# A131B.net
KiCad netlist of a schematic drawn in EAGLE
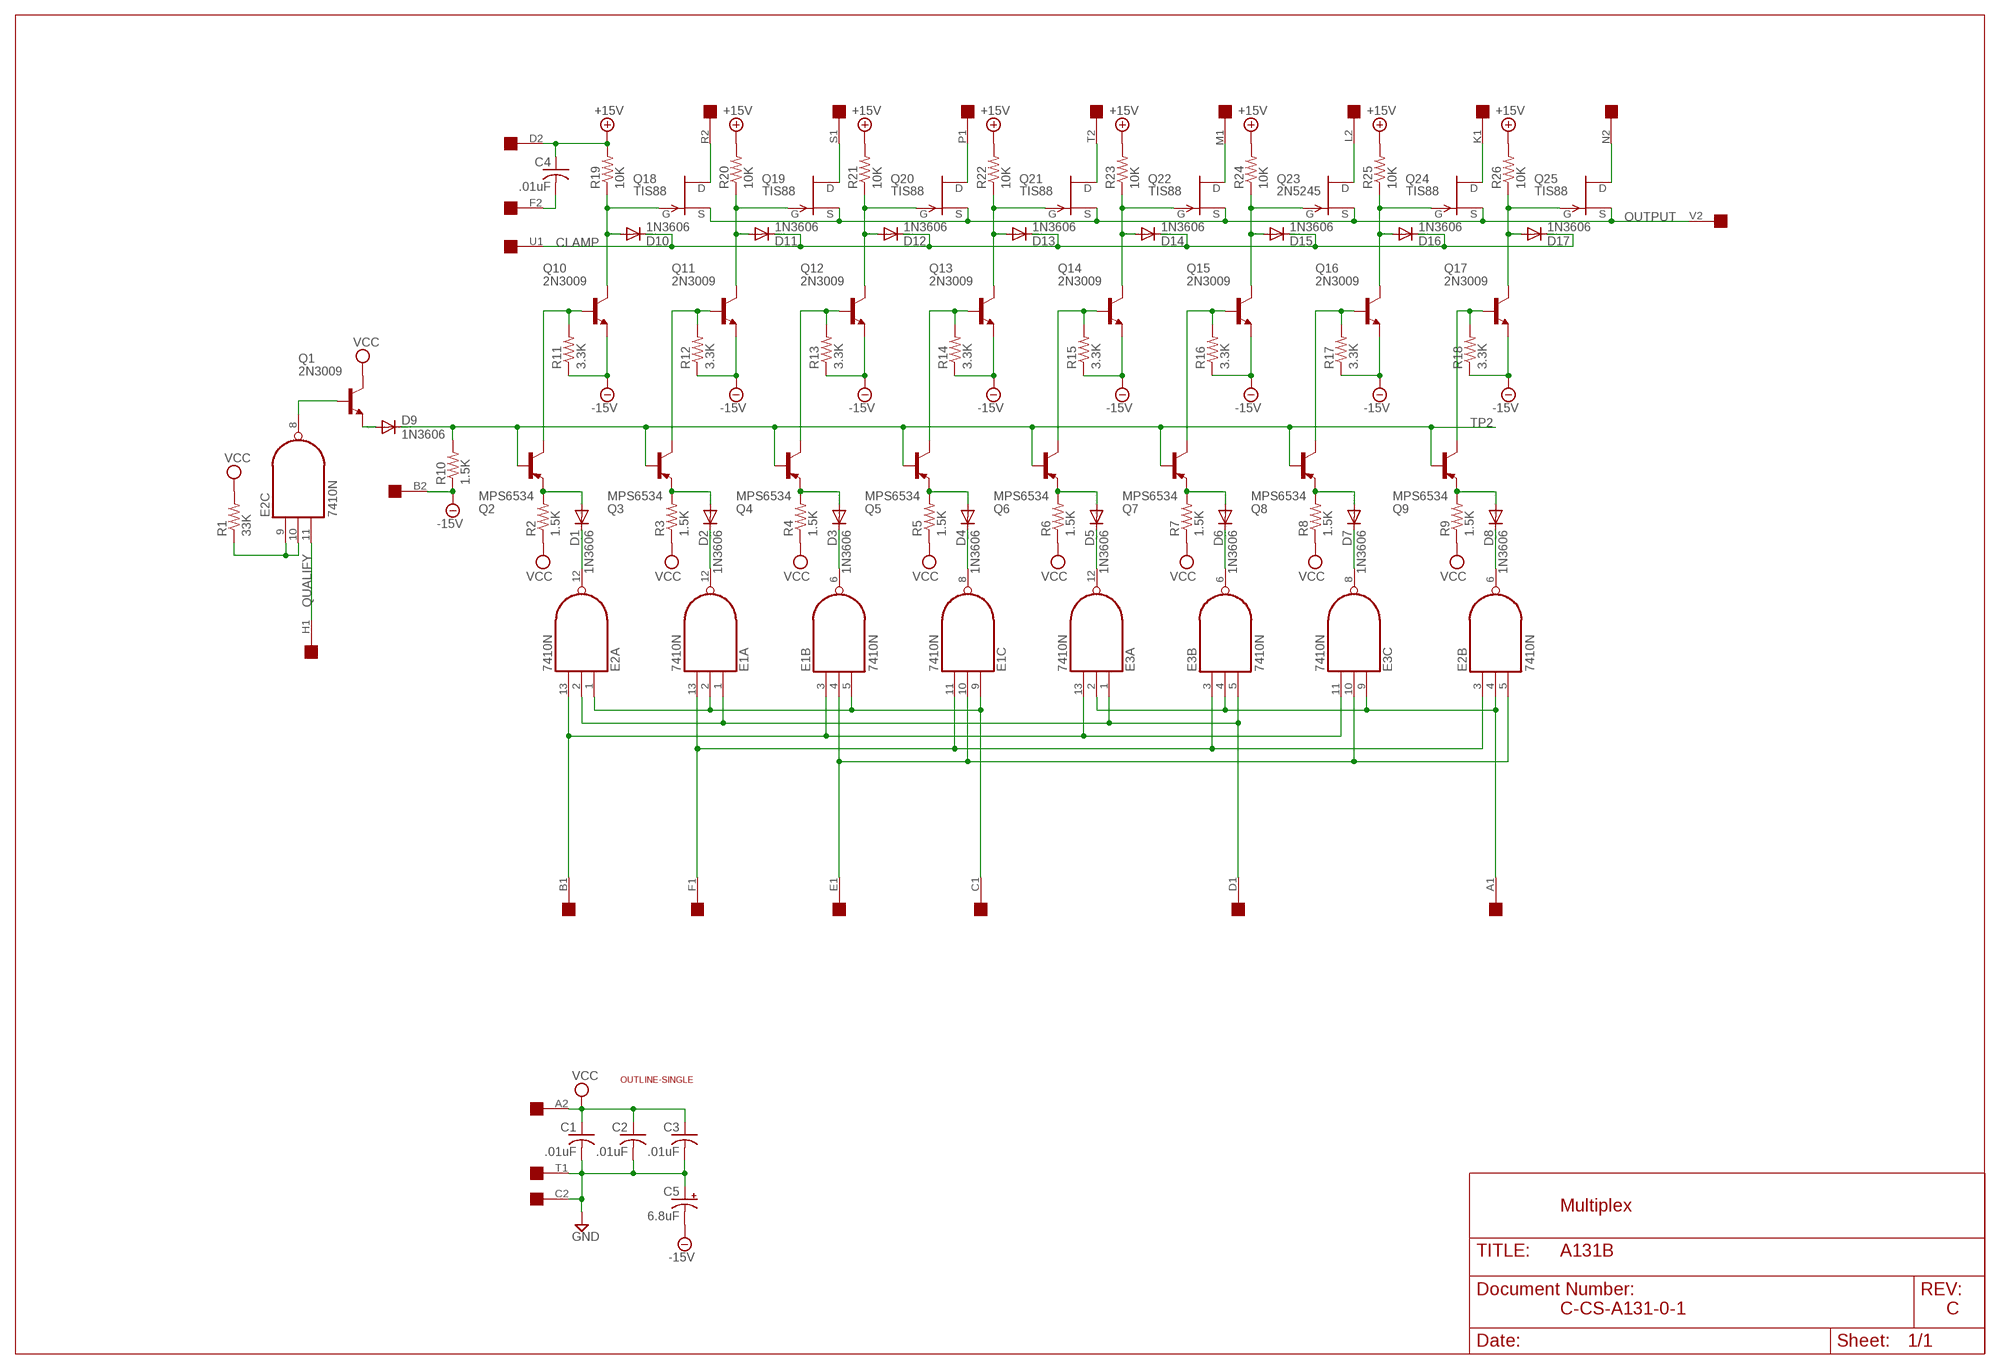
[diagram p0: schematic, sheet 1]

(export (version "E")
  (design (tool "Eeschema 10.0.6"))
  (components
    (comp (ref "C1")
      (value ".01uF")
      (footprint "eagle-import:C050-025X075")
      (libsource (lib "eagle-import") (part "C-US050-025X075"))
    )
    (comp (ref "C2")
      (value ".01uF")
      (footprint "eagle-import:C050-025X075")
      (libsource (lib "eagle-import") (part "C-US050-025X075"))
    )
    (comp (ref "C3")
      (value ".01uF")
      (footprint "eagle-import:C050-025X075")
      (libsource (lib "eagle-import") (part "C-US050-025X075"))
    )
    (comp (ref "C4")
      (value ".01uF")
      (footprint "eagle-import:C050-025X075")
      (libsource (lib "eagle-import") (part "C-US050-025X075"))
    )
    (comp (ref "C5")
      (value "6.8uF")
      (footprint "eagle-import:E12-8")
      (libsource (lib "eagle-import") (part "CPOL-USE20-8AXIAL"))
    )
    (comp (ref "D1")
      (value "1N3606")
      (footprint "eagle-import:DO35-10")
      (libsource (lib "eagle-import") (part "DIODE-DO35-10"))
    )
    (comp (ref "D2")
      (value "1N3606")
      (footprint "eagle-import:DO35-10")
      (libsource (lib "eagle-import") (part "DIODE-DO35-10"))
    )
    (comp (ref "D3")
      (value "1N3606")
      (footprint "eagle-import:DO35-10")
      (libsource (lib "eagle-import") (part "DIODE-DO35-10"))
    )
    (comp (ref "D4")
      (value "1N3606")
      (footprint "eagle-import:DO35-10")
      (libsource (lib "eagle-import") (part "DIODE-DO35-10"))
    )
    (comp (ref "D5")
      (value "1N3606")
      (footprint "eagle-import:DO35-10")
      (libsource (lib "eagle-import") (part "DIODE-DO35-10"))
    )
    (comp (ref "D6")
      (value "1N3606")
      (footprint "eagle-import:DO35-10")
      (libsource (lib "eagle-import") (part "DIODE-DO35-10"))
    )
    (comp (ref "D7")
      (value "1N3606")
      (footprint "eagle-import:DO35-10")
      (libsource (lib "eagle-import") (part "DIODE-DO35-10"))
    )
    (comp (ref "D8")
      (value "1N3606")
      (footprint "eagle-import:DO35-10")
      (libsource (lib "eagle-import") (part "DIODE-DO35-10"))
    )
    (comp (ref "D9")
      (value "1N3606")
      (footprint "eagle-import:DO35-10")
      (libsource (lib "eagle-import") (part "DIODE-DO35-10"))
    )
    (comp (ref "D10")
      (value "1N3606")
      (footprint "eagle-import:DO35-10")
      (libsource (lib "eagle-import") (part "DIODE-DO35-10"))
    )
    (comp (ref "D11")
      (value "1N3606")
      (footprint "eagle-import:DO35-10")
      (libsource (lib "eagle-import") (part "DIODE-DO35-10"))
    )
    (comp (ref "D12")
      (value "1N3606")
      (footprint "eagle-import:DO35-10")
      (libsource (lib "eagle-import") (part "DIODE-DO35-10"))
    )
    (comp (ref "D13")
      (value "1N3606")
      (footprint "eagle-import:DO35-10")
      (libsource (lib "eagle-import") (part "DIODE-DO35-10"))
    )
    (comp (ref "D14")
      (value "1N3606")
      (footprint "eagle-import:DO35-10")
      (libsource (lib "eagle-import") (part "DIODE-DO35-10"))
    )
    (comp (ref "D15")
      (value "1N3606")
      (footprint "eagle-import:DO35-10")
      (libsource (lib "eagle-import") (part "DIODE-DO35-10"))
    )
    (comp (ref "D16")
      (value "1N3606")
      (footprint "eagle-import:DO35-10")
      (libsource (lib "eagle-import") (part "DIODE-DO35-10"))
    )
    (comp (ref "D17")
      (value "1N3606")
      (footprint "eagle-import:DO35-10")
      (libsource (lib "eagle-import") (part "DIODE-DO35-10"))
    )
    (comp (ref "E1")
      (value "7410N")
      (footprint "eagle-import:DIL14")
      (libsource (lib "eagle-import") (part "7410N"))
    )
    (comp (ref "E2")
      (value "7410N")
      (footprint "eagle-import:DIL14")
      (libsource (lib "eagle-import") (part "7410N"))
    )
    (comp (ref "E3")
      (value "7410N")
      (footprint "eagle-import:DIL14")
      (libsource (lib "eagle-import") (part "7410N"))
    )
    (comp (ref "Q1")
      (value "2N3009")
      (footprint "eagle-import:TO5")
      (libsource (lib "eagle-import") (part "-NPN-TO5"))
    )
    (comp (ref "Q2")
      (value "MPS6534")
      (footprint "eagle-import:TO5")
      (libsource (lib "eagle-import") (part "-PNP-TO5"))
    )
    (comp (ref "Q3")
      (value "MPS6534")
      (footprint "eagle-import:TO5")
      (libsource (lib "eagle-import") (part "-PNP-TO5"))
    )
    (comp (ref "Q4")
      (value "MPS6534")
      (footprint "eagle-import:TO5")
      (libsource (lib "eagle-import") (part "-PNP-TO5"))
    )
    (comp (ref "Q5")
      (value "MPS6534")
      (footprint "eagle-import:TO5")
      (libsource (lib "eagle-import") (part "-PNP-TO5"))
    )
    (comp (ref "Q6")
      (value "MPS6534")
      (footprint "eagle-import:TO5")
      (libsource (lib "eagle-import") (part "-PNP-TO5"))
    )
    (comp (ref "Q7")
      (value "MPS6534")
      (footprint "eagle-import:TO5")
      (libsource (lib "eagle-import") (part "-PNP-TO5"))
    )
    (comp (ref "Q8")
      (value "MPS6534")
      (footprint "eagle-import:TO5")
      (libsource (lib "eagle-import") (part "-PNP-TO5"))
    )
    (comp (ref "Q9")
      (value "MPS6534")
      (footprint "eagle-import:TO5")
      (libsource (lib "eagle-import") (part "-PNP-TO5"))
    )
    (comp (ref "Q10")
      (value "2N3009")
      (footprint "eagle-import:TO5")
      (libsource (lib "eagle-import") (part "-NPN-TO5"))
    )
    (comp (ref "Q11")
      (value "2N3009")
      (footprint "eagle-import:TO5")
      (libsource (lib "eagle-import") (part "-NPN-TO5"))
    )
    (comp (ref "Q12")
      (value "2N3009")
      (footprint "eagle-import:TO5")
      (libsource (lib "eagle-import") (part "-NPN-TO5"))
    )
    (comp (ref "Q13")
      (value "2N3009")
      (footprint "eagle-import:TO5")
      (libsource (lib "eagle-import") (part "-NPN-TO5"))
    )
    (comp (ref "Q14")
      (value "2N3009")
      (footprint "eagle-import:TO5")
      (libsource (lib "eagle-import") (part "-NPN-TO5"))
    )
    (comp (ref "Q15")
      (value "2N3009")
      (footprint "eagle-import:TO5")
      (libsource (lib "eagle-import") (part "-NPN-TO5"))
    )
    (comp (ref "Q16")
      (value "2N3009")
      (footprint "eagle-import:TO5")
      (libsource (lib "eagle-import") (part "-NPN-TO5"))
    )
    (comp (ref "Q17")
      (value "2N3009")
      (footprint "eagle-import:TO5")
      (libsource (lib "eagle-import") (part "-NPN-TO5"))
    )
    (comp (ref "Q18")
      (value "TIS88")
      (footprint "eagle-import:TO39")
      (libsource (lib "eagle-import") (part "TIS88"))
    )
    (comp (ref "Q19")
      (value "TIS88")
      (footprint "eagle-import:TO39")
      (libsource (lib "eagle-import") (part "TIS88"))
    )
    (comp (ref "Q20")
      (value "TIS88")
      (footprint "eagle-import:TO39")
      (libsource (lib "eagle-import") (part "TIS88"))
    )
    (comp (ref "Q21")
      (value "TIS88")
      (footprint "eagle-import:TO39")
      (libsource (lib "eagle-import") (part "TIS88"))
    )
    (comp (ref "Q22")
      (value "TIS88")
      (footprint "eagle-import:TO39")
      (libsource (lib "eagle-import") (part "TIS88"))
    )
    (comp (ref "Q23")
      (value "2N5245")
      (footprint "eagle-import:TO39")
      (libsource (lib "eagle-import") (part "TIS88"))
    )
    (comp (ref "Q24")
      (value "TIS88")
      (footprint "eagle-import:TO39")
      (libsource (lib "eagle-import") (part "TIS88"))
    )
    (comp (ref "Q25")
      (value "TIS88")
      (footprint "eagle-import:TO39")
      (libsource (lib "eagle-import") (part "TIS88"))
    )
    (comp (ref "R1")
      (value "33K")
      (footprint "eagle-import:0207_10")
      (libsource (lib "eagle-import") (part "R-US_0207/10"))
    )
    (comp (ref "R2")
      (value "1.5K")
      (footprint "eagle-import:0207_10")
      (libsource (lib "eagle-import") (part "R-US_0207/10"))
    )
    (comp (ref "R3")
      (value "1.5K")
      (footprint "eagle-import:0207_10")
      (libsource (lib "eagle-import") (part "R-US_0207/10"))
    )
    (comp (ref "R4")
      (value "1.5K")
      (footprint "eagle-import:0207_10")
      (libsource (lib "eagle-import") (part "R-US_0207/10"))
    )
    (comp (ref "R5")
      (value "1.5K")
      (footprint "eagle-import:0207_10")
      (libsource (lib "eagle-import") (part "R-US_0207/10"))
    )
    (comp (ref "R6")
      (value "1.5K")
      (footprint "eagle-import:0207_10")
      (libsource (lib "eagle-import") (part "R-US_0207/10"))
    )
    (comp (ref "R7")
      (value "1.5K")
      (footprint "eagle-import:0207_10")
      (libsource (lib "eagle-import") (part "R-US_0207/10"))
    )
    (comp (ref "R8")
      (value "1.5K")
      (footprint "eagle-import:0207_10")
      (libsource (lib "eagle-import") (part "R-US_0207/10"))
    )
    (comp (ref "R9")
      (value "1.5K")
      (footprint "eagle-import:0207_10")
      (libsource (lib "eagle-import") (part "R-US_0207/10"))
    )
    (comp (ref "R10")
      (value "1.5K")
      (footprint "eagle-import:0207_10")
      (libsource (lib "eagle-import") (part "R-US_0207/10"))
    )
    (comp (ref "R11")
      (value "3.3K")
      (footprint "eagle-import:0207_10")
      (libsource (lib "eagle-import") (part "R-US_0207/10"))
    )
    (comp (ref "R12")
      (value "3.3K")
      (footprint "eagle-import:0207_10")
      (libsource (lib "eagle-import") (part "R-US_0207/10"))
    )
    (comp (ref "R13")
      (value "3.3K")
      (footprint "eagle-import:0207_10")
      (libsource (lib "eagle-import") (part "R-US_0207/10"))
    )
    (comp (ref "R14")
      (value "3.3K")
      (footprint "eagle-import:0207_10")
      (libsource (lib "eagle-import") (part "R-US_0207/10"))
    )
    (comp (ref "R15")
      (value "3.3K")
      (footprint "eagle-import:0207_10")
      (libsource (lib "eagle-import") (part "R-US_0207/10"))
    )
    (comp (ref "R16")
      (value "3.3K")
      (footprint "eagle-import:0207_10")
      (libsource (lib "eagle-import") (part "R-US_0207/10"))
    )
    (comp (ref "R17")
      (value "3.3K")
      (footprint "eagle-import:0207_10")
      (libsource (lib "eagle-import") (part "R-US_0207/10"))
    )
    (comp (ref "R18")
      (value "3.3K")
      (footprint "eagle-import:0207_10")
      (libsource (lib "eagle-import") (part "R-US_0207/10"))
    )
    (comp (ref "R19")
      (value "10K")
      (footprint "eagle-import:0207_10")
      (libsource (lib "eagle-import") (part "R-US_0207/10"))
    )
    (comp (ref "R20")
      (value "10K")
      (footprint "eagle-import:0207_10")
      (libsource (lib "eagle-import") (part "R-US_0207/10"))
    )
    (comp (ref "R21")
      (value "10K")
      (footprint "eagle-import:0207_10")
      (libsource (lib "eagle-import") (part "R-US_0207/10"))
    )
    (comp (ref "R22")
      (value "10K")
      (footprint "eagle-import:0207_10")
      (libsource (lib "eagle-import") (part "R-US_0207/10"))
    )
    (comp (ref "R23")
      (value "10K")
      (footprint "eagle-import:0207_10")
      (libsource (lib "eagle-import") (part "R-US_0207/10"))
    )
    (comp (ref "R24")
      (value "10K")
      (footprint "eagle-import:0207_10")
      (libsource (lib "eagle-import") (part "R-US_0207/10"))
    )
    (comp (ref "R25")
      (value "10K")
      (footprint "eagle-import:0207_10")
      (libsource (lib "eagle-import") (part "R-US_0207/10"))
    )
    (comp (ref "R26")
      (value "10K")
      (footprint "eagle-import:0207_10")
      (libsource (lib "eagle-import") (part "R-US_0207/10"))
    )
    (comp (ref "U$1")
      (value "OUTLINE-SINGLE")
      (footprint "eagle-import:SINGLE")
      (libsource (lib "eagle-import") (part "OUTLINE-SINGLE"))
    )
    (comp (ref "U$2")
      (value "SINGLE")
      (footprint "eagle-import:EDGE-CON2")
      (libsource (lib "eagle-import") (part "SINGLE"))
    )
  )
  (nets
    (net (code "1") (name "+15V") (class "Default")
      (node (ref "C4") (pin "1") (pinfunction "1_1") (pintype "passive"))
      (node (ref "R19") (pin "2") (pinfunction "2_2") (pintype "passive"))
      (node (ref "R20") (pin "2") (pinfunction "2_2") (pintype "passive"))
      (node (ref "R21") (pin "2") (pinfunction "2_2") (pintype "passive"))
      (node (ref "R22") (pin "2") (pinfunction "2_2") (pintype "passive"))
      (node (ref "R23") (pin "2") (pinfunction "2_2") (pintype "passive"))
      (node (ref "R24") (pin "2") (pinfunction "2_2") (pintype "passive"))
      (node (ref "R25") (pin "2") (pinfunction "2_2") (pintype "passive"))
      (node (ref "R26") (pin "2") (pinfunction "2_2") (pintype "passive"))
      (node (ref "U$2") (pin "D2") (pinfunction "1_D2") (pintype "bidirectional"))
    )
    (net (code "2") (name "-15V") (class "Default")
      (node (ref "C5") (pin "-") (pinfunction "-_-") (pintype "passive"))
      (node (ref "Q10") (pin "1") (pinfunction "E_1") (pintype "passive"))
      (node (ref "Q11") (pin "1") (pinfunction "E_1") (pintype "passive"))
      (node (ref "Q12") (pin "1") (pinfunction "E_1") (pintype "passive"))
      (node (ref "Q13") (pin "1") (pinfunction "E_1") (pintype "passive"))
      (node (ref "Q14") (pin "1") (pinfunction "E_1") (pintype "passive"))
      (node (ref "Q15") (pin "1") (pinfunction "E_1") (pintype "passive"))
      (node (ref "Q16") (pin "1") (pinfunction "E_1") (pintype "passive"))
      (node (ref "Q17") (pin "1") (pinfunction "E_1") (pintype "passive"))
      (node (ref "R10") (pin "1") (pinfunction "1_1") (pintype "passive"))
      (node (ref "R11") (pin "1") (pinfunction "1_1") (pintype "passive"))
      (node (ref "R12") (pin "1") (pinfunction "1_1") (pintype "passive"))
      (node (ref "R13") (pin "1") (pinfunction "1_1") (pintype "passive"))
      (node (ref "R14") (pin "1") (pinfunction "1_1") (pintype "passive"))
      (node (ref "R15") (pin "1") (pinfunction "1_1") (pintype "passive"))
      (node (ref "R16") (pin "1") (pinfunction "1_1") (pintype "passive"))
      (node (ref "R17") (pin "1") (pinfunction "1_1") (pintype "passive"))
      (node (ref "R18") (pin "1") (pinfunction "1_1") (pintype "passive"))
      (node (ref "U$2") (pin "B2") (pinfunction "1_B2") (pintype "bidirectional"))
    )
    (net (code "3") (name "/CLAMP") (class "Default")
      (node (ref "D10") (pin "C") (pinfunction "C_C") (pintype "passive"))
      (node (ref "D11") (pin "C") (pinfunction "C_C") (pintype "passive"))
      (node (ref "D12") (pin "C") (pinfunction "C_C") (pintype "passive"))
      (node (ref "D13") (pin "C") (pinfunction "C_C") (pintype "passive"))
      (node (ref "D14") (pin "C") (pinfunction "C_C") (pintype "passive"))
      (node (ref "D15") (pin "C") (pinfunction "C_C") (pintype "passive"))
      (node (ref "D16") (pin "C") (pinfunction "C_C") (pintype "passive"))
      (node (ref "D17") (pin "C") (pinfunction "C_C") (pintype "passive"))
      (node (ref "U$2") (pin "U1") (pinfunction "1_U1") (pintype "bidirectional"))
    )
    (net (code "4") (name "/OUTPUT") (class "Default")
      (node (ref "Q18") (pin "1") (pinfunction "S_1") (pintype "passive"))
      (node (ref "Q19") (pin "1") (pinfunction "S_1") (pintype "passive"))
      (node (ref "Q20") (pin "1") (pinfunction "S_1") (pintype "passive"))
      (node (ref "Q21") (pin "1") (pinfunction "S_1") (pintype "passive"))
      (node (ref "Q22") (pin "1") (pinfunction "S_1") (pintype "passive"))
      (node (ref "Q23") (pin "1") (pinfunction "S_1") (pintype "passive"))
      (node (ref "Q24") (pin "1") (pinfunction "S_1") (pintype "passive"))
      (node (ref "Q25") (pin "1") (pinfunction "S_1") (pintype "passive"))
      (node (ref "U$2") (pin "V2") (pinfunction "1_V2") (pintype "bidirectional"))
    )
    (net (code "5") (name "/QUALIFY") (class "Default")
      (node (ref "E2") (pin "11") (pinfunction "I2_11") (pintype "input"))
      (node (ref "U$2") (pin "H1") (pinfunction "1_H1") (pintype "bidirectional"))
    )
    (net (code "6") (name "/TP2") (class "Default")
      (node (ref "D9") (pin "C") (pinfunction "C_C") (pintype "passive"))
      (node (ref "Q2") (pin "2") (pinfunction "B_2") (pintype "passive"))
      (node (ref "Q3") (pin "2") (pinfunction "B_2") (pintype "passive"))
      (node (ref "Q4") (pin "2") (pinfunction "B_2") (pintype "passive"))
      (node (ref "Q5") (pin "2") (pinfunction "B_2") (pintype "passive"))
      (node (ref "Q6") (pin "2") (pinfunction "B_2") (pintype "passive"))
      (node (ref "Q7") (pin "2") (pinfunction "B_2") (pintype "passive"))
      (node (ref "Q8") (pin "2") (pinfunction "B_2") (pintype "passive"))
      (node (ref "Q9") (pin "2") (pinfunction "B_2") (pintype "passive"))
      (node (ref "R10") (pin "2") (pinfunction "2_2") (pintype "passive"))
    )
    (net (code "7") (name "GND") (class "Default")
      (node (ref "C1") (pin "2") (pinfunction "2_2") (pintype "passive"))
      (node (ref "C2") (pin "2") (pinfunction "2_2") (pintype "passive"))
      (node (ref "C3") (pin "2") (pinfunction "2_2") (pintype "passive"))
      (node (ref "C5") (pin "+") (pinfunction "+_+") (pintype "passive"))
      (node (ref "U$2") (pin "C2") (pinfunction "1_C2") (pintype "bidirectional"))
      (node (ref "U$2") (pin "T1") (pinfunction "1_T1") (pintype "bidirectional"))
    )
    (net (code "8") (name "Net-(E1A-I0)") (class "Default")
      (node (ref "E1") (pin "1") (pinfunction "I0_1") (pintype "input"))
      (node (ref "E2") (pin "2") (pinfunction "I1_2") (pintype "input"))
      (node (ref "E3") (pin "1") (pinfunction "I0_1") (pintype "input"))
      (node (ref "E3") (pin "5") (pinfunction "I2_5") (pintype "input"))
      (node (ref "U$2") (pin "D1") (pinfunction "1_D1") (pintype "bidirectional"))
    )
    (net (code "9") (name "Net-(E1A-I1)") (class "Default")
      (node (ref "E1") (pin "2") (pinfunction "I1_2") (pintype "input"))
      (node (ref "E1") (pin "5") (pinfunction "I2_5") (pintype "input"))
      (node (ref "E1") (pin "9") (pinfunction "I0_9") (pintype "input"))
      (node (ref "E2") (pin "1") (pinfunction "I0_1") (pintype "input"))
      (node (ref "U$2") (pin "C1") (pinfunction "1_C1") (pintype "bidirectional"))
    )
    (net (code "10") (name "Net-(E1A-I2)") (class "Default")
      (node (ref "E1") (pin "11") (pinfunction "I2_11") (pintype "input"))
      (node (ref "E1") (pin "13") (pinfunction "I2_13") (pintype "input"))
      (node (ref "E2") (pin "3") (pinfunction "I0_3") (pintype "input"))
      (node (ref "E3") (pin "3") (pinfunction "I0_3") (pintype "input"))
      (node (ref "U$2") (pin "F1") (pinfunction "1_F1") (pintype "bidirectional"))
    )
    (net (code "11") (name "Net-(E1A-O)") (class "Default")
      (node (ref "D2") (pin "C") (pinfunction "C_C") (pintype "passive"))
      (node (ref "E1") (pin "12") (pinfunction "O_12") (pintype "output"))
    )
    (net (code "12") (name "Net-(E1B-I0)") (class "Default")
      (node (ref "E1") (pin "3") (pinfunction "I0_3") (pintype "input"))
      (node (ref "E2") (pin "13") (pinfunction "I2_13") (pintype "input"))
      (node (ref "E3") (pin "11") (pinfunction "I2_11") (pintype "input"))
      (node (ref "E3") (pin "13") (pinfunction "I2_13") (pintype "input"))
      (node (ref "U$2") (pin "B1") (pinfunction "1_B1") (pintype "bidirectional"))
    )
    (net (code "13") (name "Net-(E1B-I1)") (class "Default")
      (node (ref "E1") (pin "10") (pinfunction "I1_10") (pintype "input"))
      (node (ref "E1") (pin "4") (pinfunction "I1_4") (pintype "input"))
      (node (ref "E2") (pin "5") (pinfunction "I2_5") (pintype "input"))
      (node (ref "E3") (pin "10") (pinfunction "I1_10") (pintype "input"))
      (node (ref "U$2") (pin "E1") (pinfunction "1_E1") (pintype "bidirectional"))
    )
    (net (code "14") (name "Net-(E1B-O)") (class "Default")
      (node (ref "D3") (pin "C") (pinfunction "C_C") (pintype "passive"))
      (node (ref "E1") (pin "6") (pinfunction "O_6") (pintype "output"))
    )
    (net (code "15") (name "Net-(E1C-O)") (class "Default")
      (node (ref "D4") (pin "C") (pinfunction "C_C") (pintype "passive"))
      (node (ref "E1") (pin "8") (pinfunction "O_8") (pintype "output"))
    )
    (net (code "16") (name "Net-(E2A-O)") (class "Default")
      (node (ref "D1") (pin "C") (pinfunction "C_C") (pintype "passive"))
      (node (ref "E2") (pin "12") (pinfunction "O_12") (pintype "output"))
    )
    (net (code "17") (name "Net-(E2B-I1)") (class "Default")
      (node (ref "E2") (pin "4") (pinfunction "I1_4") (pintype "input"))
      (node (ref "E3") (pin "2") (pinfunction "I1_2") (pintype "input"))
      (node (ref "E3") (pin "4") (pinfunction "I1_4") (pintype "input"))
      (node (ref "E3") (pin "9") (pinfunction "I0_9") (pintype "input"))
      (node (ref "U$2") (pin "A1") (pinfunction "1_A1") (pintype "bidirectional"))
    )
    (net (code "18") (name "Net-(E2B-O)") (class "Default")
      (node (ref "D8") (pin "C") (pinfunction "C_C") (pintype "passive"))
      (node (ref "E2") (pin "6") (pinfunction "O_6") (pintype "output"))
    )
    (net (code "19") (name "Net-(E2C-I0)") (class "Default")
      (node (ref "E2") (pin "10") (pinfunction "I1_10") (pintype "input"))
      (node (ref "E2") (pin "9") (pinfunction "I0_9") (pintype "input"))
      (node (ref "R1") (pin "1") (pinfunction "1_1") (pintype "passive"))
    )
    (net (code "20") (name "Net-(E2C-O)") (class "Default")
      (node (ref "E2") (pin "8") (pinfunction "O_8") (pintype "output"))
      (node (ref "Q1") (pin "2") (pinfunction "B_2") (pintype "passive"))
    )
    (net (code "21") (name "Net-(E3A-O)") (class "Default")
      (node (ref "D5") (pin "C") (pinfunction "C_C") (pintype "passive"))
      (node (ref "E3") (pin "12") (pinfunction "O_12") (pintype "output"))
    )
    (net (code "22") (name "Net-(E3B-O)") (class "Default")
      (node (ref "D6") (pin "C") (pinfunction "C_C") (pintype "passive"))
      (node (ref "E3") (pin "6") (pinfunction "O_6") (pintype "output"))
    )
    (net (code "23") (name "Net-(E3C-O)") (class "Default")
      (node (ref "D7") (pin "C") (pinfunction "C_C") (pintype "passive"))
      (node (ref "E3") (pin "8") (pinfunction "O_8") (pintype "output"))
    )
    (net (code "24") (name "Net-(Q1-E)") (class "Default")
      (node (ref "D9") (pin "A") (pinfunction "A_A") (pintype "passive"))
      (node (ref "Q1") (pin "1") (pinfunction "E_1") (pintype "passive"))
    )
    (net (code "25") (name "Net-(Q2-E)") (class "Default")
      (node (ref "D1") (pin "A") (pinfunction "A_A") (pintype "passive"))
      (node (ref "Q2") (pin "1") (pinfunction "E_1") (pintype "passive"))
      (node (ref "R2") (pin "2") (pinfunction "2_2") (pintype "passive"))
    )
    (net (code "26") (name "Net-(Q3-E)") (class "Default")
      (node (ref "D2") (pin "A") (pinfunction "A_A") (pintype "passive"))
      (node (ref "Q3") (pin "1") (pinfunction "E_1") (pintype "passive"))
      (node (ref "R3") (pin "2") (pinfunction "2_2") (pintype "passive"))
    )
    (net (code "27") (name "Net-(Q4-E)") (class "Default")
      (node (ref "D3") (pin "A") (pinfunction "A_A") (pintype "passive"))
      (node (ref "Q4") (pin "1") (pinfunction "E_1") (pintype "passive"))
      (node (ref "R4") (pin "2") (pinfunction "2_2") (pintype "passive"))
    )
    (net (code "28") (name "Net-(Q5-E)") (class "Default")
      (node (ref "D4") (pin "A") (pinfunction "A_A") (pintype "passive"))
      (node (ref "Q5") (pin "1") (pinfunction "E_1") (pintype "passive"))
      (node (ref "R5") (pin "2") (pinfunction "2_2") (pintype "passive"))
    )
    (net (code "29") (name "Net-(Q6-E)") (class "Default")
      (node (ref "D5") (pin "A") (pinfunction "A_A") (pintype "passive"))
      (node (ref "Q6") (pin "1") (pinfunction "E_1") (pintype "passive"))
      (node (ref "R6") (pin "2") (pinfunction "2_2") (pintype "passive"))
    )
    (net (code "30") (name "Net-(Q7-E)") (class "Default")
      (node (ref "D6") (pin "A") (pinfunction "A_A") (pintype "passive"))
      (node (ref "Q7") (pin "1") (pinfunction "E_1") (pintype "passive"))
      (node (ref "R7") (pin "2") (pinfunction "2_2") (pintype "passive"))
    )
    (net (code "31") (name "Net-(Q8-E)") (class "Default")
      (node (ref "D7") (pin "A") (pinfunction "A_A") (pintype "passive"))
      (node (ref "Q8") (pin "1") (pinfunction "E_1") (pintype "passive"))
      (node (ref "R8") (pin "2") (pinfunction "2_2") (pintype "passive"))
    )
    (net (code "32") (name "Net-(Q9-E)") (class "Default")
      (node (ref "D8") (pin "A") (pinfunction "A_A") (pintype "passive"))
      (node (ref "Q9") (pin "1") (pinfunction "E_1") (pintype "passive"))
      (node (ref "R9") (pin "2") (pinfunction "2_2") (pintype "passive"))
    )
    (net (code "33") (name "Net-(Q10-B)") (class "Default")
      (node (ref "Q10") (pin "2") (pinfunction "B_2") (pintype "passive"))
      (node (ref "Q2") (pin "3") (pinfunction "C_3") (pintype "passive"))
      (node (ref "R11") (pin "2") (pinfunction "2_2") (pintype "passive"))
    )
    (net (code "34") (name "Net-(Q10-C)") (class "Default")
      (node (ref "D10") (pin "A") (pinfunction "A_A") (pintype "passive"))
      (node (ref "Q10") (pin "3") (pinfunction "C_3") (pintype "passive"))
      (node (ref "Q18") (pin "3") (pinfunction "G_3") (pintype "passive"))
      (node (ref "R19") (pin "1") (pinfunction "1_1") (pintype "passive"))
    )
    (net (code "35") (name "Net-(Q11-B)") (class "Default")
      (node (ref "Q11") (pin "2") (pinfunction "B_2") (pintype "passive"))
      (node (ref "Q3") (pin "3") (pinfunction "C_3") (pintype "passive"))
      (node (ref "R12") (pin "2") (pinfunction "2_2") (pintype "passive"))
    )
    (net (code "36") (name "Net-(Q11-C)") (class "Default")
      (node (ref "D11") (pin "A") (pinfunction "A_A") (pintype "passive"))
      (node (ref "Q11") (pin "3") (pinfunction "C_3") (pintype "passive"))
      (node (ref "Q19") (pin "3") (pinfunction "G_3") (pintype "passive"))
      (node (ref "R20") (pin "1") (pinfunction "1_1") (pintype "passive"))
    )
    (net (code "37") (name "Net-(Q12-B)") (class "Default")
      (node (ref "Q12") (pin "2") (pinfunction "B_2") (pintype "passive"))
      (node (ref "Q4") (pin "3") (pinfunction "C_3") (pintype "passive"))
      (node (ref "R13") (pin "2") (pinfunction "2_2") (pintype "passive"))
    )
    (net (code "38") (name "Net-(Q12-C)") (class "Default")
      (node (ref "D12") (pin "A") (pinfunction "A_A") (pintype "passive"))
      (node (ref "Q12") (pin "3") (pinfunction "C_3") (pintype "passive"))
      (node (ref "Q20") (pin "3") (pinfunction "G_3") (pintype "passive"))
      (node (ref "R21") (pin "1") (pinfunction "1_1") (pintype "passive"))
    )
    (net (code "39") (name "Net-(Q13-B)") (class "Default")
      (node (ref "Q13") (pin "2") (pinfunction "B_2") (pintype "passive"))
      (node (ref "Q5") (pin "3") (pinfunction "C_3") (pintype "passive"))
      (node (ref "R14") (pin "2") (pinfunction "2_2") (pintype "passive"))
    )
    (net (code "40") (name "Net-(Q13-C)") (class "Default")
      (node (ref "D13") (pin "A") (pinfunction "A_A") (pintype "passive"))
      (node (ref "Q13") (pin "3") (pinfunction "C_3") (pintype "passive"))
      (node (ref "Q21") (pin "3") (pinfunction "G_3") (pintype "passive"))
      (node (ref "R22") (pin "1") (pinfunction "1_1") (pintype "passive"))
    )
    (net (code "41") (name "Net-(Q14-B)") (class "Default")
      (node (ref "Q14") (pin "2") (pinfunction "B_2") (pintype "passive"))
      (node (ref "Q6") (pin "3") (pinfunction "C_3") (pintype "passive"))
      (node (ref "R15") (pin "2") (pinfunction "2_2") (pintype "passive"))
    )
    (net (code "42") (name "Net-(Q14-C)") (class "Default")
      (node (ref "D14") (pin "A") (pinfunction "A_A") (pintype "passive"))
      (node (ref "Q14") (pin "3") (pinfunction "C_3") (pintype "passive"))
      (node (ref "Q22") (pin "3") (pinfunction "G_3") (pintype "passive"))
      (node (ref "R23") (pin "1") (pinfunction "1_1") (pintype "passive"))
    )
    (net (code "43") (name "Net-(Q15-B)") (class "Default")
      (node (ref "Q15") (pin "2") (pinfunction "B_2") (pintype "passive"))
      (node (ref "Q7") (pin "3") (pinfunction "C_3") (pintype "passive"))
      (node (ref "R16") (pin "2") (pinfunction "2_2") (pintype "passive"))
    )
    (net (code "44") (name "Net-(Q15-C)") (class "Default")
      (node (ref "D15") (pin "A") (pinfunction "A_A") (pintype "passive"))
      (node (ref "Q15") (pin "3") (pinfunction "C_3") (pintype "passive"))
      (node (ref "Q23") (pin "3") (pinfunction "G_3") (pintype "passive"))
      (node (ref "R24") (pin "1") (pinfunction "1_1") (pintype "passive"))
    )
    (net (code "45") (name "Net-(Q16-B)") (class "Default")
      (node (ref "Q16") (pin "2") (pinfunction "B_2") (pintype "passive"))
      (node (ref "Q8") (pin "3") (pinfunction "C_3") (pintype "passive"))
      (node (ref "R17") (pin "2") (pinfunction "2_2") (pintype "passive"))
    )
    (net (code "46") (name "Net-(Q16-C)") (class "Default")
      (node (ref "D16") (pin "A") (pinfunction "A_A") (pintype "passive"))
      (node (ref "Q16") (pin "3") (pinfunction "C_3") (pintype "passive"))
      (node (ref "Q24") (pin "3") (pinfunction "G_3") (pintype "passive"))
      (node (ref "R25") (pin "1") (pinfunction "1_1") (pintype "passive"))
    )
    (net (code "47") (name "Net-(Q17-B)") (class "Default")
      (node (ref "Q17") (pin "2") (pinfunction "B_2") (pintype "passive"))
      (node (ref "Q9") (pin "3") (pinfunction "C_3") (pintype "passive"))
      (node (ref "R18") (pin "2") (pinfunction "2_2") (pintype "passive"))
    )
    (net (code "48") (name "Net-(Q17-C)") (class "Default")
      (node (ref "D17") (pin "A") (pinfunction "A_A") (pintype "passive"))
      (node (ref "Q17") (pin "3") (pinfunction "C_3") (pintype "passive"))
      (node (ref "Q25") (pin "3") (pinfunction "G_3") (pintype "passive"))
      (node (ref "R26") (pin "1") (pinfunction "1_1") (pintype "passive"))
    )
    (net (code "49") (name "Net-(Q18-D)") (class "Default")
      (node (ref "Q18") (pin "2") (pinfunction "D_2") (pintype "passive"))
      (node (ref "U$2") (pin "R2") (pinfunction "1_R2") (pintype "bidirectional"))
    )
    (net (code "50") (name "Net-(Q19-D)") (class "Default")
      (node (ref "Q19") (pin "2") (pinfunction "D_2") (pintype "passive"))
      (node (ref "U$2") (pin "S1") (pinfunction "1_S1") (pintype "bidirectional"))
    )
    (net (code "51") (name "Net-(Q20-D)") (class "Default")
      (node (ref "Q20") (pin "2") (pinfunction "D_2") (pintype "passive"))
      (node (ref "U$2") (pin "P1") (pinfunction "1_P1") (pintype "bidirectional"))
    )
    (net (code "52") (name "Net-(Q21-D)") (class "Default")
      (node (ref "Q21") (pin "2") (pinfunction "D_2") (pintype "passive"))
      (node (ref "U$2") (pin "T2") (pinfunction "1_T2") (pintype "bidirectional"))
    )
    (net (code "53") (name "Net-(Q22-D)") (class "Default")
      (node (ref "Q22") (pin "2") (pinfunction "D_2") (pintype "passive"))
      (node (ref "U$2") (pin "M1") (pinfunction "1_M1") (pintype "bidirectional"))
    )
    (net (code "54") (name "Net-(Q23-D)") (class "Default")
      (node (ref "Q23") (pin "2") (pinfunction "D_2") (pintype "passive"))
      (node (ref "U$2") (pin "L2") (pinfunction "1_L2") (pintype "bidirectional"))
    )
    (net (code "55") (name "Net-(Q24-D)") (class "Default")
      (node (ref "Q24") (pin "2") (pinfunction "D_2") (pintype "passive"))
      (node (ref "U$2") (pin "K1") (pinfunction "1_K1") (pintype "bidirectional"))
    )
    (net (code "56") (name "Net-(Q25-D)") (class "Default")
      (node (ref "Q25") (pin "2") (pinfunction "D_2") (pintype "passive"))
      (node (ref "U$2") (pin "N2") (pinfunction "1_N2") (pintype "bidirectional"))
    )
    (net (code "57") (name "Net-(U$2L-1)") (class "Default")
      (node (ref "C4") (pin "2") (pinfunction "2_2") (pintype "passive"))
      (node (ref "U$2") (pin "F2") (pinfunction "1_F2") (pintype "bidirectional"))
    )
    (net (code "58") (name "VCC") (class "Default")
      (node (ref "C1") (pin "1") (pinfunction "1_1") (pintype "passive"))
      (node (ref "C2") (pin "1") (pinfunction "1_1") (pintype "passive"))
      (node (ref "C3") (pin "1") (pinfunction "1_1") (pintype "passive"))
      (node (ref "Q1") (pin "3") (pinfunction "C_3") (pintype "passive"))
      (node (ref "R1") (pin "2") (pinfunction "2_2") (pintype "passive"))
      (node (ref "R2") (pin "1") (pinfunction "1_1") (pintype "passive"))
      (node (ref "R3") (pin "1") (pinfunction "1_1") (pintype "passive"))
      (node (ref "R4") (pin "1") (pinfunction "1_1") (pintype "passive"))
      (node (ref "R5") (pin "1") (pinfunction "1_1") (pintype "passive"))
      (node (ref "R6") (pin "1") (pinfunction "1_1") (pintype "passive"))
      (node (ref "R7") (pin "1") (pinfunction "1_1") (pintype "passive"))
      (node (ref "R8") (pin "1") (pinfunction "1_1") (pintype "passive"))
      (node (ref "R9") (pin "1") (pinfunction "1_1") (pintype "passive"))
      (node (ref "U$2") (pin "A2") (pinfunction "1_A2") (pintype "bidirectional"))
    )
  )
)
